# CK2150_BT.net
KiCad netlist of a schematic drawn in EAGLE
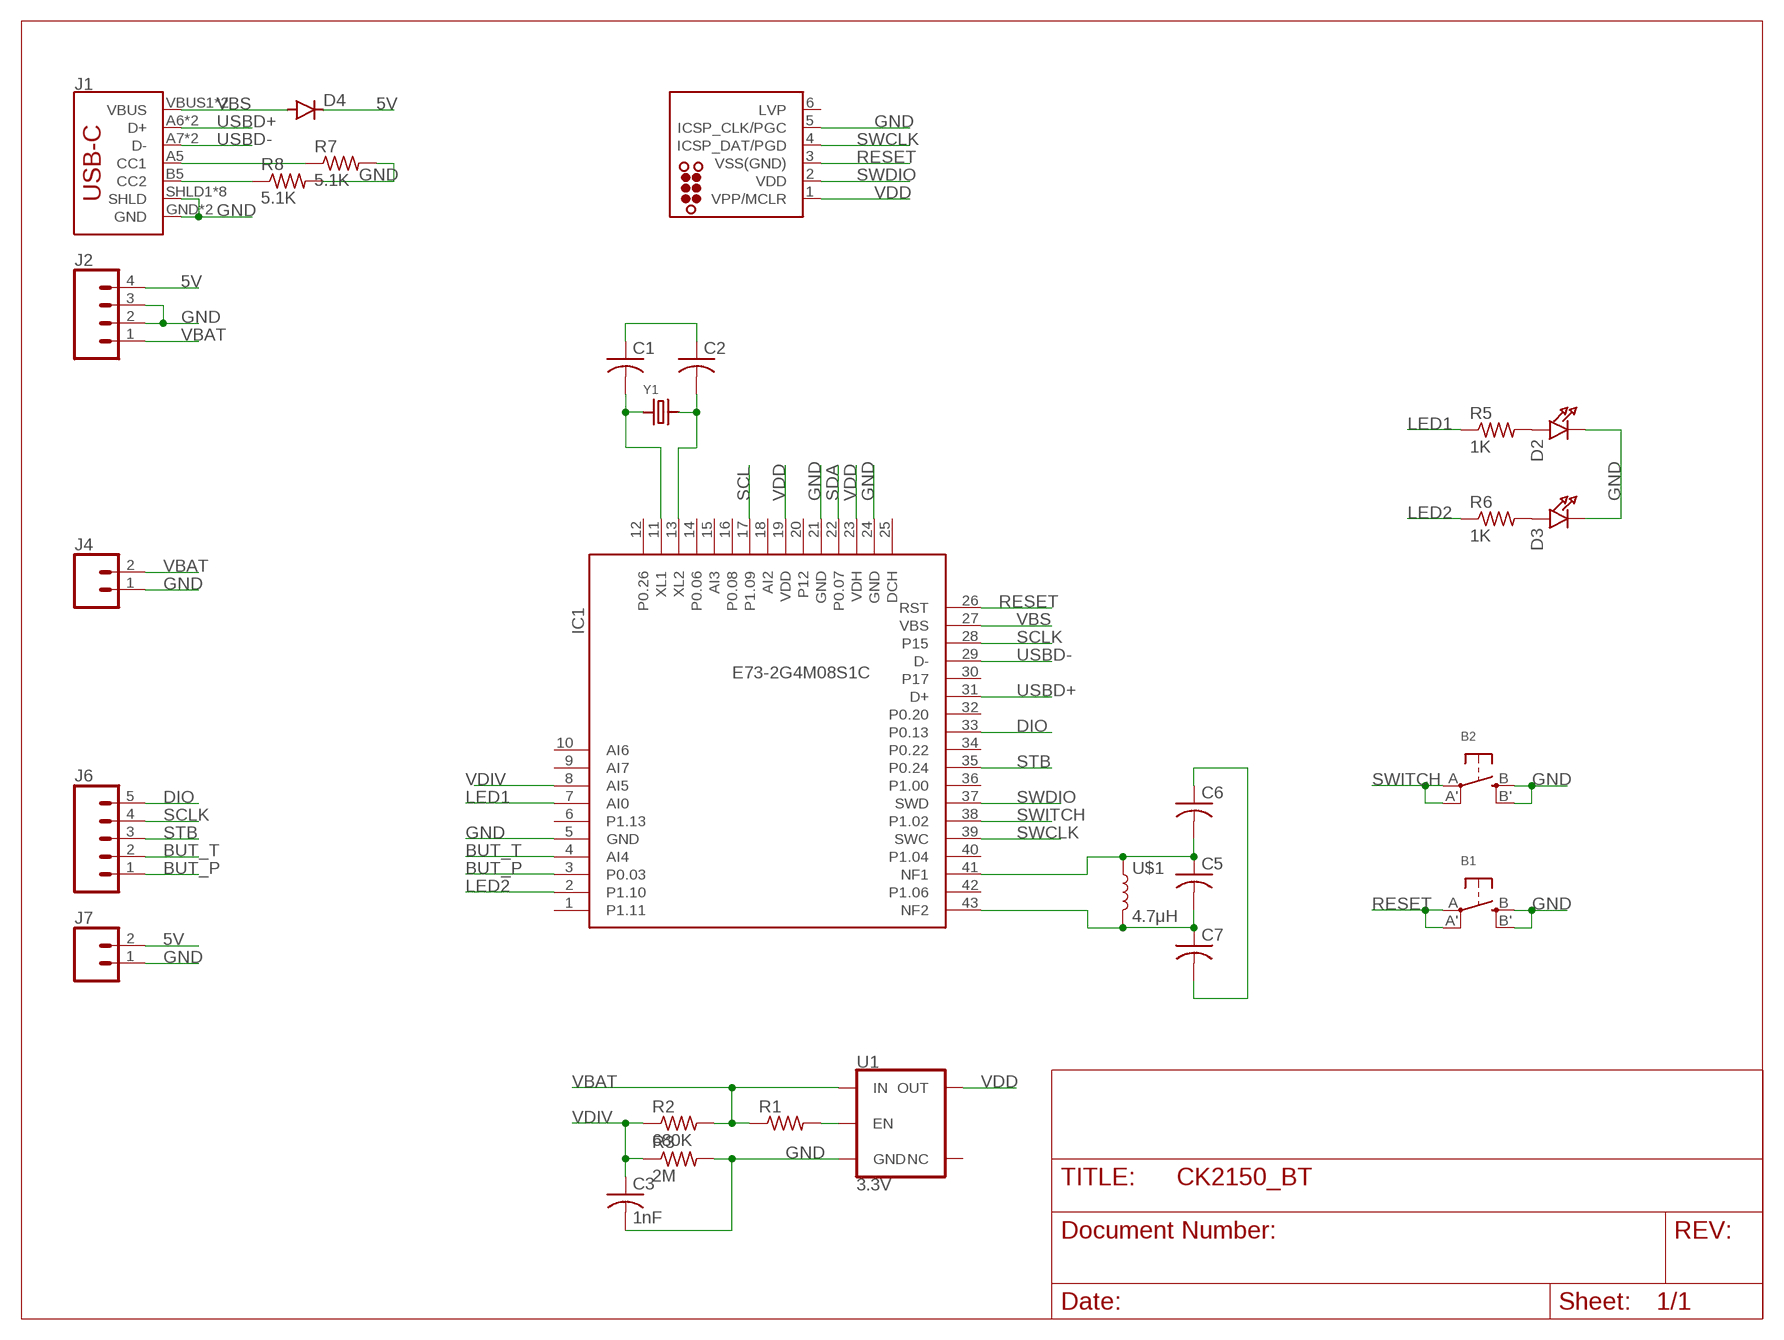
[diagram p0: schematic, sheet 1]

(export (version "E")
  (design (tool "Eeschema 10.0.6"))
  (components
    (comp (ref "B1")
      (value "SWITCH_TACT_SMT4.6X2.8")
      (footprint "eagle-import:BTN_KMR2_4.6X2.8")
      (libsource (lib "eagle-import") (part "SWITCH_TACT_SMT4.6X2.8"))
    )
    (comp (ref "B2")
      (value "SWITCH_TACT_SMT4.6X2.8")
      (footprint "eagle-import:BTN_KMR2_4.6X2.8")
      (libsource (lib "eagle-import") (part "SWITCH_TACT_SMT4.6X2.8"))
    )
    (comp (ref "C1")
      (value "C-USC0603")
      (footprint "eagle-import:C0603")
      (libsource (lib "eagle-import") (part "C-USC0603"))
    )
    (comp (ref "C2")
      (value "C-USC0603")
      (footprint "eagle-import:C0603")
      (libsource (lib "eagle-import") (part "C-USC0603"))
    )
    (comp (ref "C3")
      (value "1nF")
      (footprint "eagle-import:C0603")
      (libsource (lib "eagle-import") (part "C-USC0603"))
    )
    (comp (ref "C5")
      (value "C-USC0603")
      (footprint "eagle-import:C0603")
      (libsource (lib "eagle-import") (part "C-USC0603"))
    )
    (comp (ref "C6")
      (value "C-USC0603")
      (footprint "eagle-import:C0603")
      (libsource (lib "eagle-import") (part "C-USC0603"))
    )
    (comp (ref "C7")
      (value "C-USC0603")
      (footprint "eagle-import:C0603")
      (libsource (lib "eagle-import") (part "C-USC0603"))
    )
    (comp (ref "D2")
      (value "LED0805_NOOUTLINE")
      (footprint "eagle-import:CHIPLED_0805_NOOUTLINE")
      (libsource (lib "eagle-import") (part "LED0805_NOOUTLINE"))
    )
    (comp (ref "D3")
      (value "LED0805_NOOUTLINE")
      (footprint "eagle-import:CHIPLED_0805_NOOUTLINE")
      (libsource (lib "eagle-import") (part "LED0805_NOOUTLINE"))
    )
    (comp (ref "D4")
      (value "DIODE-SOD123")
      (footprint "eagle-import:SOD123")
      (libsource (lib "eagle-import") (part "DIODE-SOD123"))
    )
    (comp (ref "IC1")
      (value "E73-2G4M08S1C")
      (footprint "eagle-import:SMD")
      (libsource (lib "eagle-import") (part "E73-2G4M08S1C"))
    )
    (comp (ref "J1")
      (value "USB_C5")
      (footprint "eagle-import:USB-C-16P-5")
      (libsource (lib "eagle-import") (part "USB_C5"))
    )
    (comp (ref "J2")
      (value "CONN_041X04_NO_SILK")
      (footprint "eagle-import:1X04_NO_SILK")
      (libsource (lib "eagle-import") (part "CONN_041X04_NO_SILK"))
    )
    (comp (ref "J3")
      (value "TC2030-MCP-NL")
      (footprint "eagle-import:TC2030-MCP-NL")
      (libsource (lib "eagle-import") (part "TC2030-MCP-NL"))
    )
    (comp (ref "J4")
      (value "CONN_021X02_NO_SILK")
      (footprint "eagle-import:1X02_NO_SILK")
      (libsource (lib "eagle-import") (part "CONN_021X02_NO_SILK"))
    )
    (comp (ref "J6")
      (value "CONN_05NO_SILK")
      (footprint "eagle-import:1X05_NO_SILK")
      (libsource (lib "eagle-import") (part "CONN_05NO_SILK"))
    )
    (comp (ref "J7")
      (value "CONN_021X02_NO_SILK")
      (footprint "eagle-import:1X02_NO_SILK")
      (libsource (lib "eagle-import") (part "CONN_021X02_NO_SILK"))
    )
    (comp (ref "R1")
      (value "R-US_R0603")
      (footprint "eagle-import:R0603")
      (libsource (lib "eagle-import") (part "R-US_R0603"))
    )
    (comp (ref "R2")
      (value "680K")
      (footprint "eagle-import:R0603")
      (libsource (lib "eagle-import") (part "R-US_R0603"))
    )
    (comp (ref "R3")
      (value "2M")
      (footprint "eagle-import:R0603")
      (libsource (lib "eagle-import") (part "R-US_R0603"))
    )
    (comp (ref "R5")
      (value "1K")
      (footprint "eagle-import:R0603")
      (libsource (lib "eagle-import") (part "R-US_R0603"))
    )
    (comp (ref "R6")
      (value "1K")
      (footprint "eagle-import:R0603")
      (libsource (lib "eagle-import") (part "R-US_R0603"))
    )
    (comp (ref "R7")
      (value "5.1K")
      (footprint "eagle-import:R0603")
      (libsource (lib "eagle-import") (part "R-US_R0603"))
    )
    (comp (ref "R8")
      (value "5.1K")
      (footprint "eagle-import:R0603")
      (libsource (lib "eagle-import") (part "R-US_R0603"))
    )
    (comp (ref "U$1")
      (value "4.7μH")
      (footprint "eagle-import:W3102")
      (libsource (lib "eagle-import") (part "RFID_ANTENNA_W3102"))
    )
    (comp (ref "U1")
      (value "3.3V")
      (footprint "eagle-import:SOT23-5")
      (libsource (lib "eagle-import") (part "V_REG_AP2112K-3.3V"))
    )
    (comp (ref "Y1")
      (value "CRYSTAL8X3.8SMT")
      (footprint "eagle-import:CRYSTAL_8X3.8")
      (libsource (lib "eagle-import") (part "CRYSTAL8X3.8SMT"))
    )
  )
  (nets
    (net (code "1") (name "/5V") (class "Default")
      (node (ref "D4") (pin "C") (pinfunction "C_C") (pintype "passive"))
      (node (ref "J2") (pin "4") (pinfunction "4_4") (pintype "passive"))
      (node (ref "J7") (pin "2") (pinfunction "2_2") (pintype "passive"))
    )
    (net (code "2") (name "/BUT_P") (class "Default")
      (node (ref "IC1") (pin "3") (pinfunction "P0.03_3") (pintype "bidirectional"))
      (node (ref "J6") (pin "1") (pinfunction "1_1") (pintype "passive"))
    )
    (net (code "3") (name "/BUT_T") (class "Default")
      (node (ref "IC1") (pin "4") (pinfunction "AI4_4") (pintype "bidirectional"))
      (node (ref "J6") (pin "2") (pinfunction "2_2") (pintype "passive"))
    )
    (net (code "4") (name "/DIO") (class "Default")
      (node (ref "IC1") (pin "33") (pinfunction "P0.13_33") (pintype "bidirectional"))
      (node (ref "J6") (pin "5") (pinfunction "5_5") (pintype "passive"))
    )
    (net (code "5") (name "/GND") (class "Default")
      (node (ref "B1") (pin "B") (pinfunction "S_B") (pintype "passive"))
      (node (ref "B1") (pin "B'") (pinfunction "S1_B'") (pintype "passive"))
      (node (ref "B2") (pin "B") (pinfunction "S_B") (pintype "passive"))
      (node (ref "B2") (pin "B'") (pinfunction "S1_B'") (pintype "passive"))
      (node (ref "C1") (pin "1") (pinfunction "1_1") (pintype "passive"))
      (node (ref "C2") (pin "1") (pinfunction "1_1") (pintype "passive"))
      (node (ref "C3") (pin "2") (pinfunction "2_2") (pintype "passive"))
      (node (ref "C6") (pin "1") (pinfunction "1_1") (pintype "passive"))
      (node (ref "C7") (pin "2") (pinfunction "2_2") (pintype "passive"))
      (node (ref "D2") (pin "C") (pinfunction "C_C") (pintype "passive"))
      (node (ref "D3") (pin "C") (pinfunction "C_C") (pintype "passive"))
      (node (ref "IC1") (pin "21") (pinfunction "GND_21") (pintype "power_in"))
      (node (ref "IC1") (pin "24") (pinfunction "GND_24") (pintype "power_in"))
      (node (ref "IC1") (pin "5") (pinfunction "GND_5") (pintype "power_in"))
      (node (ref "J1") (pin "GND") (pinfunction "GND_GND") (pintype "bidirectional"))
      (node (ref "J1") (pin "GND2") (pinfunction "GND_GND2") (pintype "bidirectional"))
      (node (ref "J1") (pin "SHLD1") (pinfunction "SHLD_SHLD1") (pintype "bidirectional"))
      (node (ref "J1") (pin "SHLD2") (pinfunction "SHLD_SHLD2") (pintype "bidirectional"))
      (node (ref "J1") (pin "SHLD3") (pinfunction "SHLD_SHLD3") (pintype "bidirectional"))
      (node (ref "J1") (pin "SHLD4") (pinfunction "SHLD_SHLD4") (pintype "bidirectional"))
      (node (ref "J1") (pin "SHLD5") (pinfunction "SHLD_SHLD5") (pintype "bidirectional"))
      (node (ref "J1") (pin "SHLD6") (pinfunction "SHLD_SHLD6") (pintype "bidirectional"))
      (node (ref "J1") (pin "SHLD7") (pinfunction "SHLD_SHLD7") (pintype "bidirectional"))
      (node (ref "J1") (pin "SHLD8") (pinfunction "SHLD_SHLD8") (pintype "bidirectional"))
      (node (ref "J2") (pin "2") (pinfunction "2_2") (pintype "passive"))
      (node (ref "J2") (pin "3") (pinfunction "3_3") (pintype "passive"))
      (node (ref "J3") (pin "5") (pinfunction "ICSP_CLK/PGC_5") (pintype "output"))
      (node (ref "J4") (pin "1") (pinfunction "1_1") (pintype "passive"))
      (node (ref "J7") (pin "1") (pinfunction "1_1") (pintype "passive"))
      (node (ref "R3") (pin "2") (pinfunction "2_2") (pintype "passive"))
      (node (ref "R7") (pin "2") (pinfunction "2_2") (pintype "passive"))
      (node (ref "R8") (pin "2") (pinfunction "2_2") (pintype "passive"))
      (node (ref "U1") (pin "2") (pinfunction "GND_2") (pintype "input"))
    )
    (net (code "6") (name "/LED1") (class "Default")
      (node (ref "IC1") (pin "7") (pinfunction "AI0_7") (pintype "bidirectional"))
      (node (ref "R5") (pin "1") (pinfunction "1_1") (pintype "passive"))
    )
    (net (code "7") (name "/LED2") (class "Default")
      (node (ref "IC1") (pin "2") (pinfunction "P1.10_2") (pintype "bidirectional"))
      (node (ref "R6") (pin "1") (pinfunction "1_1") (pintype "passive"))
    )
    (net (code "8") (name "/RESET") (class "Default")
      (node (ref "B1") (pin "A") (pinfunction "P_A") (pintype "passive"))
      (node (ref "B1") (pin "A'") (pinfunction "P1_A'") (pintype "passive"))
      (node (ref "IC1") (pin "26") (pinfunction "RST_26") (pintype "bidirectional"))
      (node (ref "J3") (pin "3") (pinfunction "VSS(GND)_3") (pintype "power_in"))
    )
    (net (code "9") (name "/SCL") (class "Default")
      (node (ref "IC1") (pin "17") (pinfunction "P1.09_17") (pintype "bidirectional"))
    )
    (net (code "10") (name "/SCLK") (class "Default")
      (node (ref "IC1") (pin "28") (pinfunction "P15_28") (pintype "bidirectional"))
      (node (ref "J6") (pin "4") (pinfunction "4_4") (pintype "passive"))
    )
    (net (code "11") (name "/SDA") (class "Default")
      (node (ref "IC1") (pin "22") (pinfunction "P0.07_22") (pintype "bidirectional"))
    )
    (net (code "12") (name "/STB") (class "Default")
      (node (ref "IC1") (pin "35") (pinfunction "P0.24_35") (pintype "bidirectional"))
      (node (ref "J6") (pin "3") (pinfunction "3_3") (pintype "passive"))
    )
    (net (code "13") (name "/SWCLK") (class "Default")
      (node (ref "IC1") (pin "39") (pinfunction "SWC_39") (pintype "bidirectional"))
      (node (ref "J3") (pin "4") (pinfunction "ICSP_DAT/PGD_4") (pintype "bidirectional"))
    )
    (net (code "14") (name "/SWDIO") (class "Default")
      (node (ref "IC1") (pin "37") (pinfunction "SWD_37") (pintype "bidirectional"))
      (node (ref "J3") (pin "2") (pinfunction "VDD_2") (pintype "power_in"))
    )
    (net (code "15") (name "/SWITCH") (class "Default")
      (node (ref "B2") (pin "A") (pinfunction "P_A") (pintype "passive"))
      (node (ref "B2") (pin "A'") (pinfunction "P1_A'") (pintype "passive"))
      (node (ref "IC1") (pin "38") (pinfunction "P1.02_38") (pintype "bidirectional"))
    )
    (net (code "16") (name "/USBD+") (class "Default")
      (node (ref "IC1") (pin "31") (pinfunction "D+_31") (pintype "bidirectional"))
      (node (ref "J1") (pin "A6") (pinfunction "D+_A6") (pintype "bidirectional"))
      (node (ref "J1") (pin "B6") (pinfunction "D+_B6") (pintype "bidirectional"))
    )
    (net (code "17") (name "/USBD-") (class "Default")
      (node (ref "IC1") (pin "29") (pinfunction "D-_29") (pintype "bidirectional"))
      (node (ref "J1") (pin "A7") (pinfunction "D-_A7") (pintype "bidirectional"))
      (node (ref "J1") (pin "B7") (pinfunction "D-_B7") (pintype "bidirectional"))
    )
    (net (code "18") (name "/VBAT") (class "Default")
      (node (ref "J2") (pin "1") (pinfunction "1_1") (pintype "passive"))
      (node (ref "J4") (pin "2") (pinfunction "2_2") (pintype "passive"))
      (node (ref "R1") (pin "1") (pinfunction "1_1") (pintype "passive"))
      (node (ref "R2") (pin "2") (pinfunction "2_2") (pintype "passive"))
      (node (ref "U1") (pin "1") (pinfunction "IN_1") (pintype "input"))
    )
    (net (code "19") (name "/VBS") (class "Default")
      (node (ref "D4") (pin "A") (pinfunction "A_A") (pintype "passive"))
      (node (ref "IC1") (pin "27") (pinfunction "VBS_27") (pintype "power_in"))
      (node (ref "J1") (pin "VBUS1") (pinfunction "VBUS_VBUS1") (pintype "bidirectional"))
      (node (ref "J1") (pin "VBUS2") (pinfunction "VBUS_VBUS2") (pintype "bidirectional"))
    )
    (net (code "20") (name "/VDD") (class "Default")
      (node (ref "IC1") (pin "19") (pinfunction "VDD_19") (pintype "power_in"))
      (node (ref "IC1") (pin "23") (pinfunction "VDH_23") (pintype "power_in"))
      (node (ref "J3") (pin "1") (pinfunction "VPP/MCLR_1") (pintype "passive"))
      (node (ref "U1") (pin "5") (pinfunction "OUT_5") (pintype "passive"))
    )
    (net (code "21") (name "/VDIV") (class "Default")
      (node (ref "C3") (pin "1") (pinfunction "1_1") (pintype "passive"))
      (node (ref "IC1") (pin "8") (pinfunction "AI5_8") (pintype "bidirectional"))
      (node (ref "R2") (pin "1") (pinfunction "1_1") (pintype "passive"))
      (node (ref "R3") (pin "1") (pinfunction "1_1") (pintype "passive"))
    )
    (net (code "22") (name "Net-(D2-PadA)") (class "Default")
      (node (ref "D2") (pin "A") (pinfunction "A_A") (pintype "passive"))
      (node (ref "R5") (pin "2") (pinfunction "2_2") (pintype "passive"))
    )
    (net (code "23") (name "Net-(D3-PadA)") (class "Default")
      (node (ref "D3") (pin "A") (pinfunction "A_A") (pintype "passive"))
      (node (ref "R6") (pin "2") (pinfunction "2_2") (pintype "passive"))
    )
    (net (code "24") (name "Net-(IC1-NF1)") (class "Default")
      (node (ref "C5") (pin "1") (pinfunction "1_1") (pintype "passive"))
      (node (ref "C6") (pin "2") (pinfunction "2_2") (pintype "passive"))
      (node (ref "IC1") (pin "41") (pinfunction "NF1_41") (pintype "bidirectional"))
      (node (ref "U$1") (pin "1") (pinfunction "1_1") (pintype "passive"))
    )
    (net (code "25") (name "Net-(IC1-NF2)") (class "Default")
      (node (ref "C5") (pin "2") (pinfunction "2_2") (pintype "passive"))
      (node (ref "C7") (pin "1") (pinfunction "1_1") (pintype "passive"))
      (node (ref "IC1") (pin "43") (pinfunction "NF2_43") (pintype "bidirectional"))
      (node (ref "U$1") (pin "2") (pinfunction "2_2") (pintype "passive"))
    )
    (net (code "26") (name "Net-(IC1-XL1)") (class "Default")
      (node (ref "C1") (pin "2") (pinfunction "2_2") (pintype "passive"))
      (node (ref "IC1") (pin "11") (pinfunction "XL1_11") (pintype "bidirectional"))
      (node (ref "Y1") (pin "P$1") (pinfunction "1_P$1") (pintype "passive"))
    )
    (net (code "27") (name "Net-(IC1-XL2)") (class "Default")
      (node (ref "C2") (pin "2") (pinfunction "2_2") (pintype "passive"))
      (node (ref "IC1") (pin "13") (pinfunction "XL2_13") (pintype "bidirectional"))
      (node (ref "Y1") (pin "P$4") (pinfunction "2_P$4") (pintype "passive"))
    )
    (net (code "28") (name "Net-(J1-CC1)") (class "Default")
      (node (ref "J1") (pin "A5") (pinfunction "CC1_A5") (pintype "bidirectional"))
      (node (ref "R7") (pin "1") (pinfunction "1_1") (pintype "passive"))
    )
    (net (code "29") (name "Net-(J1-CC2)") (class "Default")
      (node (ref "J1") (pin "B5") (pinfunction "CC2_B5") (pintype "bidirectional"))
      (node (ref "R8") (pin "1") (pinfunction "1_1") (pintype "passive"))
    )
    (net (code "30") (name "Net-(U1-EN)") (class "Default")
      (node (ref "R1") (pin "2") (pinfunction "2_2") (pintype "passive"))
      (node (ref "U1") (pin "3") (pinfunction "EN_3") (pintype "input"))
    )
    (net (code "31") (name "unconnected-(IC1-AI2-Pad18)") (class "Default")
      (node (ref "IC1") (pin "18") (pinfunction "AI2_18") (pintype "bidirectional"))
    )
    (net (code "32") (name "unconnected-(IC1-AI3-Pad15)") (class "Default")
      (node (ref "IC1") (pin "15") (pinfunction "AI3_15") (pintype "bidirectional"))
    )
    (net (code "33") (name "unconnected-(IC1-AI6-Pad10)") (class "Default")
      (node (ref "IC1") (pin "10") (pinfunction "AI6_10") (pintype "bidirectional"))
    )
    (net (code "34") (name "unconnected-(IC1-AI7-Pad9)") (class "Default")
      (node (ref "IC1") (pin "9") (pinfunction "AI7_9") (pintype "bidirectional"))
    )
    (net (code "35") (name "unconnected-(IC1-DCH-Pad25)") (class "Default")
      (node (ref "IC1") (pin "25") (pinfunction "DCH_25") (pintype "bidirectional"))
    )
    (net (code "36") (name "unconnected-(IC1-P0.06-Pad14)") (class "Default")
      (node (ref "IC1") (pin "14") (pinfunction "P0.06_14") (pintype "bidirectional"))
    )
    (net (code "37") (name "unconnected-(IC1-P0.08-Pad16)") (class "Default")
      (node (ref "IC1") (pin "16") (pinfunction "P0.08_16") (pintype "bidirectional"))
    )
    (net (code "38") (name "unconnected-(IC1-P0.20-Pad32)") (class "Default")
      (node (ref "IC1") (pin "32") (pinfunction "P0.20_32") (pintype "bidirectional"))
    )
    (net (code "39") (name "unconnected-(IC1-P0.22-Pad34)") (class "Default")
      (node (ref "IC1") (pin "34") (pinfunction "P0.22_34") (pintype "bidirectional"))
    )
    (net (code "40") (name "unconnected-(IC1-P0.26-Pad12)") (class "Default")
      (node (ref "IC1") (pin "12") (pinfunction "P0.26_12") (pintype "bidirectional"))
    )
    (net (code "41") (name "unconnected-(IC1-P1.00-Pad36)") (class "Default")
      (node (ref "IC1") (pin "36") (pinfunction "P1.00_36") (pintype "bidirectional"))
    )
    (net (code "42") (name "unconnected-(IC1-P1.04-Pad40)") (class "Default")
      (node (ref "IC1") (pin "40") (pinfunction "P1.04_40") (pintype "bidirectional"))
    )
    (net (code "43") (name "unconnected-(IC1-P1.06-Pad42)") (class "Default")
      (node (ref "IC1") (pin "42") (pinfunction "P1.06_42") (pintype "bidirectional"))
    )
    (net (code "44") (name "unconnected-(IC1-P1.11-Pad1)") (class "Default")
      (node (ref "IC1") (pin "1") (pinfunction "P1.11_1") (pintype "bidirectional"))
    )
    (net (code "45") (name "unconnected-(IC1-P1.13-Pad6)") (class "Default")
      (node (ref "IC1") (pin "6") (pinfunction "P1.13_6") (pintype "bidirectional"))
    )
    (net (code "46") (name "unconnected-(IC1-P12-Pad20)") (class "Default")
      (node (ref "IC1") (pin "20") (pinfunction "P12_20") (pintype "bidirectional"))
    )
    (net (code "47") (name "unconnected-(IC1-P17-Pad30)") (class "Default")
      (node (ref "IC1") (pin "30") (pinfunction "P17_30") (pintype "bidirectional"))
    )
    (net (code "48") (name "unconnected-(J3-LVP-Pad6)") (class "Default")
      (node (ref "J3") (pin "6") (pinfunction "LVP_6") (pintype "bidirectional"))
    )
    (net (code "49") (name "unconnected-(U1-NC-Pad4)") (class "Default")
      (node (ref "U1") (pin "4") (pinfunction "NC_4") (pintype "no_connect"))
    )
  )
)
